# Cheer_vibes.net
KiCad netlist of a schematic drawn in EAGLE
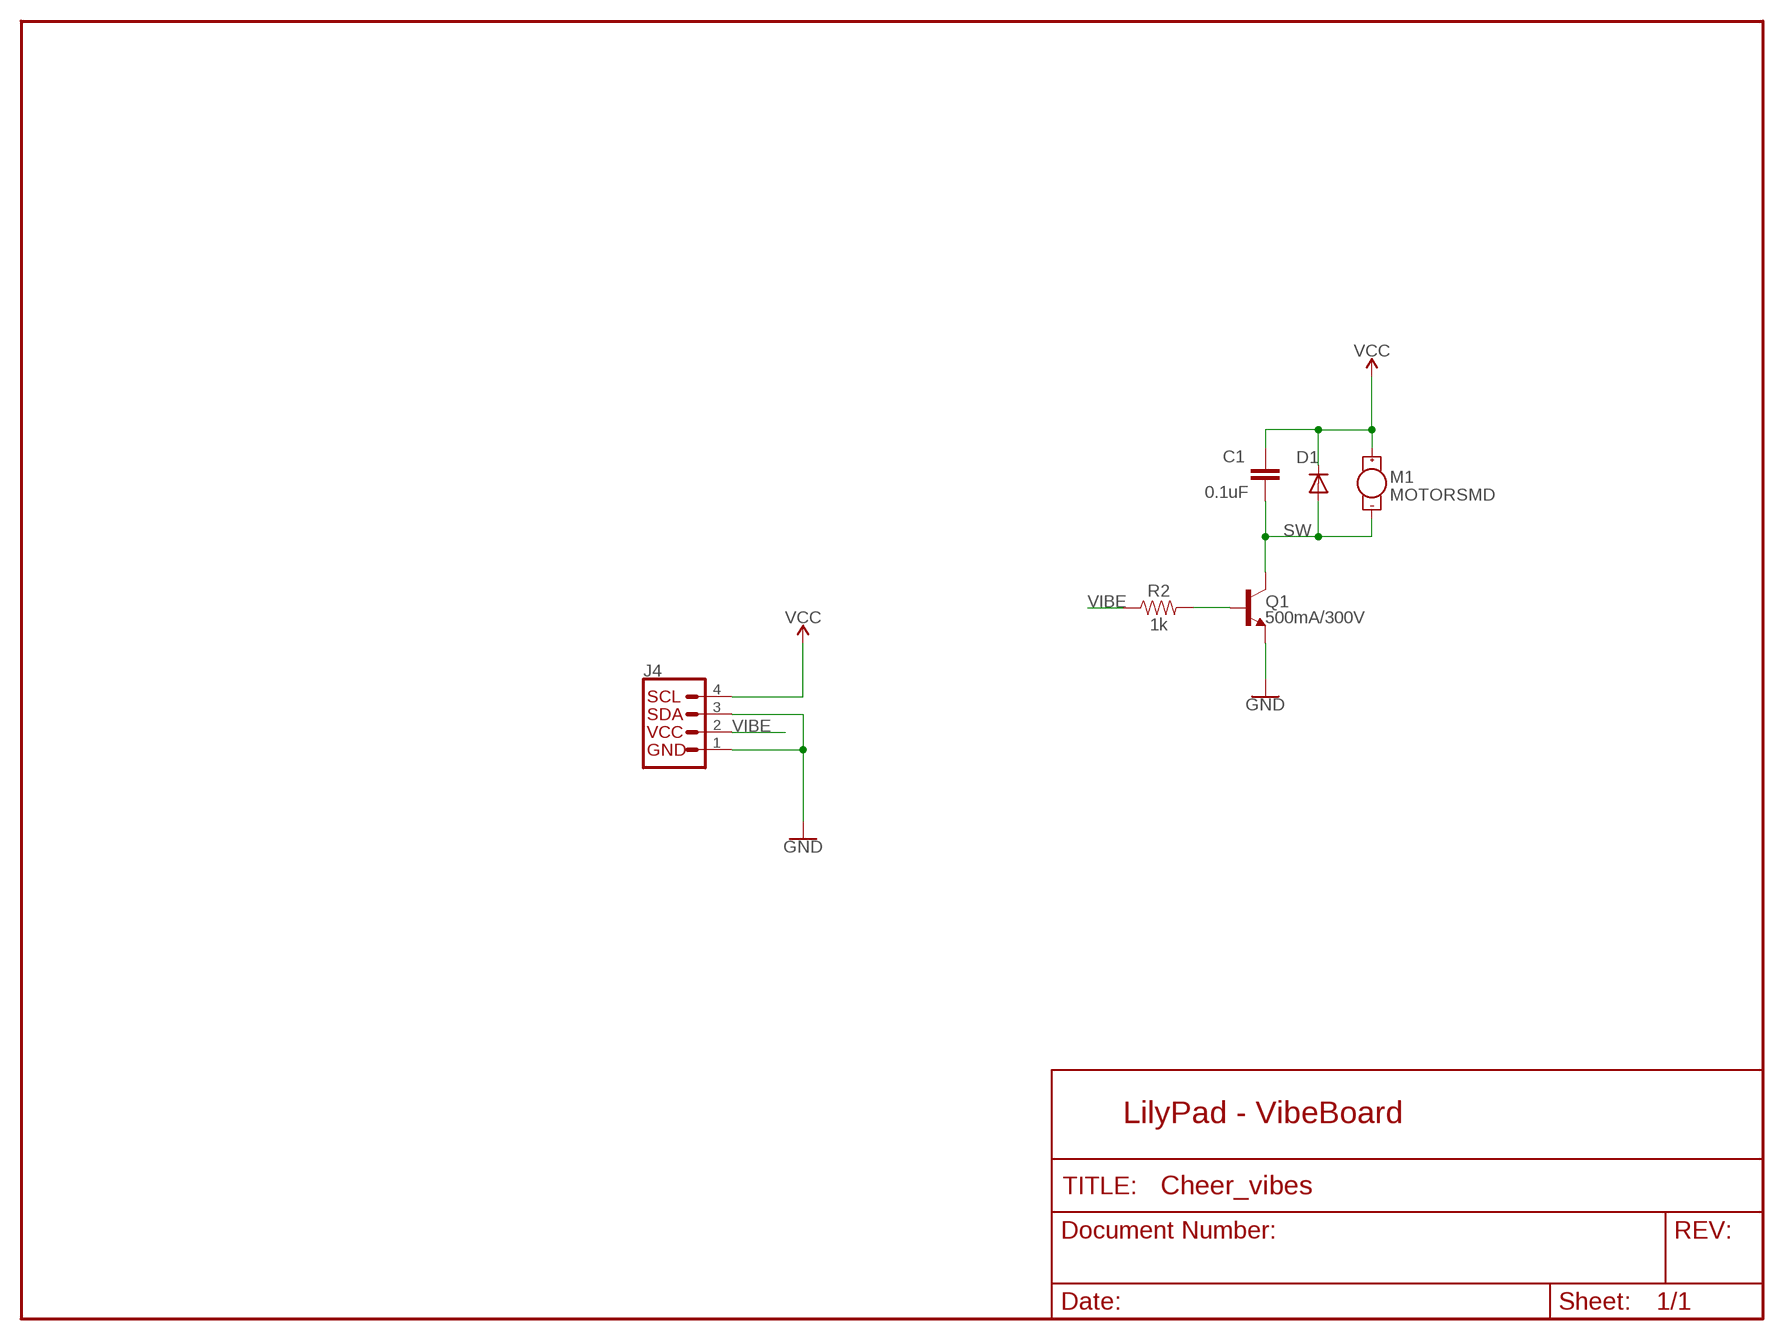
[diagram p0: schematic, sheet 1]

(export (version "E")
  (design (tool "Eeschema 10.0.6"))
  (components
    (comp (ref "C1")
      (value "0.1uF")
      (footprint "eagle-import:0603")
      (libsource (lib "eagle-import") (part "0.1UF-0603-25V-(+80/-20%)"))
    )
    (comp (ref "D1")
      (value "DIODESOD")
      (footprint "eagle-import:SOD-323")
      (libsource (lib "eagle-import") (part "DIODESOD"))
    )
    (comp (ref "J4")
      (value "QWIIC_CONNECTORJS-1MM")
      (footprint "eagle-import:1X04_1MM_RA")
      (libsource (lib "eagle-import") (part "QWIIC_CONNECTORJS-1MM"))
    )
    (comp (ref "M1")
      (value "MOTORSMD")
      (footprint "eagle-import:VIBE-MOTOR-10MM-SMD")
      (libsource (lib "eagle-import") (part "MOTORSMD"))
    )
    (comp (ref "Q1")
      (value "500mA/300V")
      (footprint "eagle-import:SOT23-3")
      (libsource (lib "eagle-import") (part "TRANS_NPN-MMBTA42"))
    )
    (comp (ref "R2")
      (value "1k")
      (footprint "eagle-import:0603")
      (libsource (lib "eagle-import") (part "1KOHM-0603-1/10W-1%"))
    )
  )
  (nets
    (net (code "1") (name "/SW") (class "Default")
      (node (ref "C1") (pin "2") (pinfunction "2_2") (pintype "passive"))
      (node (ref "D1") (pin "2") (pinfunction "A_2") (pintype "passive"))
      (node (ref "M1") (pin "P$2") (pinfunction "-_P$2") (pintype "bidirectional"))
      (node (ref "Q1") (pin "3") (pinfunction "C_3") (pintype "passive"))
    )
    (net (code "2") (name "/VIBE") (class "Default")
      (node (ref "J4") (pin "2") (pinfunction "VCC_2") (pintype "power_in"))
      (node (ref "R2") (pin "1") (pinfunction "1_1") (pintype "passive"))
    )
    (net (code "3") (name "GND") (class "Default")
      (node (ref "J4") (pin "1") (pinfunction "GND_1") (pintype "power_in"))
      (node (ref "J4") (pin "3") (pinfunction "SDA_3") (pintype "passive"))
      (node (ref "Q1") (pin "2") (pinfunction "E_2") (pintype "passive"))
    )
    (net (code "4") (name "Net-(Q1-B)") (class "Default")
      (node (ref "Q1") (pin "1") (pinfunction "B_1") (pintype "passive"))
      (node (ref "R2") (pin "2") (pinfunction "2_2") (pintype "passive"))
    )
    (net (code "5") (name "VCC") (class "Default")
      (node (ref "C1") (pin "1") (pinfunction "1_1") (pintype "passive"))
      (node (ref "D1") (pin "1") (pinfunction "C_1") (pintype "passive"))
      (node (ref "J4") (pin "4") (pinfunction "SCL_4") (pintype "passive"))
      (node (ref "M1") (pin "P$1") (pinfunction "+_P$1") (pintype "bidirectional"))
    )
  )
)
